# Sensor.net
KiCad netlist of a schematic drawn in Altium Designer
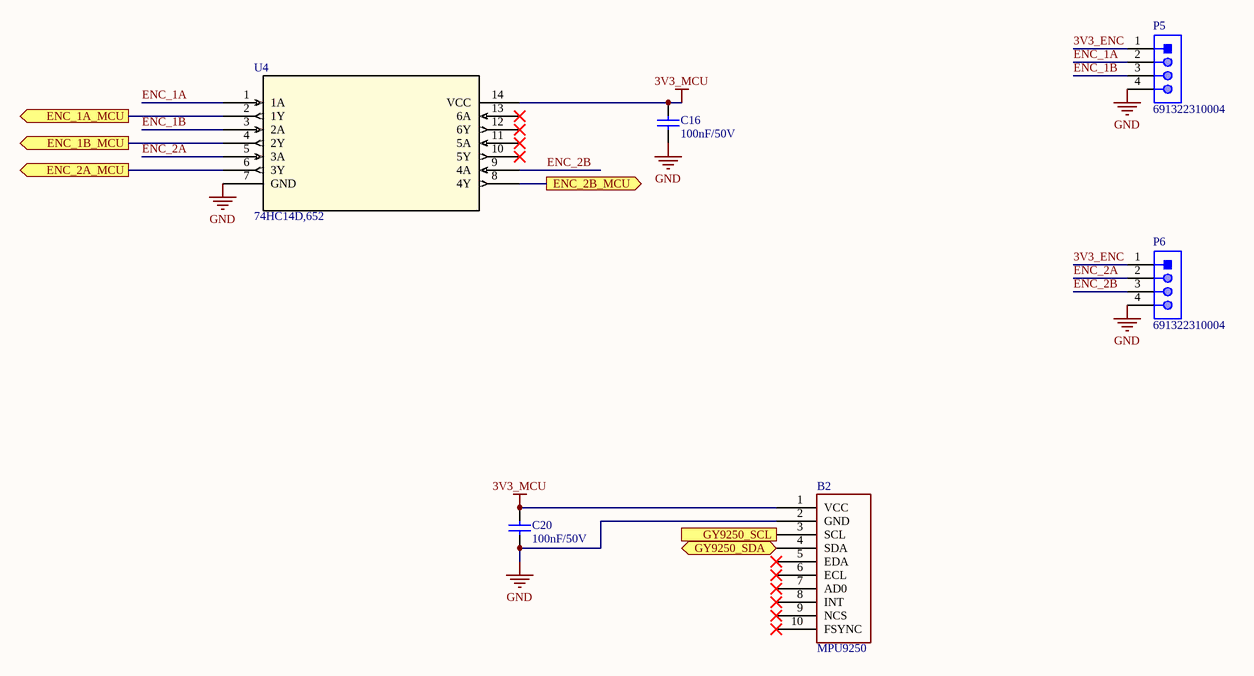
[diagram p0: Sensor.SchDoc]

(export (version "E")
  (design (tool "Eeschema 10.0.6"))
  (components
    (comp (ref "B2") (value "MPU9250") (footprint "MPU9250") (libsource (lib "Board") (part "MPU9250")))
    (comp (ref "C16")
      (value "100nF/50V")
      (footprint "CAP-SM-0805")
      (description "CAP CER 0.1UF 50V Y5V 0805")
      (fields
        (field (name "MANUFACTURER") "Samsung Electro-Mechanics")
        (field (name "MANUFACTURER PART NUMBER") "CL21F104ZBCNNNC")
      )
      (libsource (lib "Capacitor") (part "Cap-100nF-50V-0805"))
    )
    (comp (ref "C20")
      (value "100nF/50V")
      (footprint "CAP-SM-0805")
      (description "CAP CER 0.1UF 50V Y5V 0805")
      (fields
        (field (name "MANUFACTURER") "Samsung Electro-Mechanics")
        (field (name "MANUFACTURER PART NUMBER") "CL21F104ZBCNNNC")
      )
      (libsource (lib "Capacitor") (part "Cap-100nF-50V-0805"))
    )
    (comp (ref "P5")
      (value "691322310004")
      (footprint "691322310004")
      (description "WR-TBL Serie 322 Horizontal PCB Header, Pluggable, pitch 3.81mm, 4p")
      (fields (field (name "PUBLISHER") "Wurth Elektronik"))
      (libsource (lib "Domino_5mm_691101710002_Altium_WR-TBL_rev19a") (part "691322310004"))
    )
    (comp (ref "P6")
      (value "691322310004")
      (footprint "691322310004")
      (description "WR-TBL Serie 322 Horizontal PCB Header, Pluggable, pitch 3.81mm, 4p")
      (fields (field (name "PUBLISHER") "Wurth Elektronik"))
      (libsource (lib "Domino_5mm_691101710002_Altium_WR-TBL_rev19a") (part "691322310004"))
    )
    (comp (ref "U4")
      (value "74HC14D,652")
      (footprint "SOT108-1_NEX")
      (description "No Description Available")
      (fields (field (name "COPYRIGHT") "Copyright (C) 2016 Accelerated Designs. All rights reserved"))
      (libsource (lib "74HC14D_625_2020-06-19_15-46-23") (part "74HC14D,652"))
    )
  )
  (nets
    (net (code "1") (name "/3V3_ENC") (class "Default")
      (node (ref "P5") (pin "1") (pinfunction "1_1") (pintype "passive"))
      (node (ref "P6") (pin "1") (pinfunction "1_1") (pintype "passive"))
    )
    (net (code "2") (name "/ENC_1A") (class "Default")
      (node (ref "P5") (pin "2") (pinfunction "2_2") (pintype "passive"))
      (node (ref "U4") (pin "1") (pinfunction "1A_1") (pintype "input"))
    )
    (net (code "3") (name "/ENC_1A_MCU") (class "Default")
      (node (ref "U4") (pin "2") (pinfunction "1Y_2") (pintype "output"))
    )
    (net (code "4") (name "/ENC_1B") (class "Default")
      (node (ref "P5") (pin "3") (pinfunction "3_3") (pintype "passive"))
      (node (ref "U4") (pin "3") (pinfunction "2A_3") (pintype "input"))
    )
    (net (code "5") (name "/ENC_1B_MCU") (class "Default")
      (node (ref "U4") (pin "4") (pinfunction "2Y_4") (pintype "output"))
    )
    (net (code "6") (name "/ENC_2A") (class "Default")
      (node (ref "P6") (pin "2") (pinfunction "2_2") (pintype "passive"))
      (node (ref "U4") (pin "5") (pinfunction "3A_5") (pintype "input"))
    )
    (net (code "7") (name "/ENC_2A_MCU") (class "Default")
      (node (ref "U4") (pin "6") (pinfunction "3Y_6") (pintype "output"))
    )
    (net (code "8") (name "/ENC_2B") (class "Default")
      (node (ref "P6") (pin "3") (pinfunction "3_3") (pintype "passive"))
      (node (ref "U4") (pin "9") (pinfunction "4A_9") (pintype "input"))
    )
    (net (code "9") (name "/ENC_2B_MCU") (class "Default")
      (node (ref "U4") (pin "8") (pinfunction "4Y_8") (pintype "output"))
    )
    (net (code "10") (name "/GY9250_SCL") (class "Default")
      (node (ref "B2") (pin "3") (pinfunction "SCL_3") (pintype "passive"))
    )
    (net (code "11") (name "/GY9250_SDA") (class "Default")
      (node (ref "B2") (pin "4") (pinfunction "SDA_4") (pintype "passive"))
    )
    (net (code "12") (name "3V3_MCU") (class "Default")
      (node (ref "B2") (pin "1") (pinfunction "VCC_1") (pintype "passive"))
      (node (ref "C16") (pin "2") (pinfunction "2_2") (pintype "passive"))
      (node (ref "C20") (pin "2") (pinfunction "2_2") (pintype "passive"))
      (node (ref "U4") (pin "14") (pinfunction "VCC_14") (pintype "power_in"))
    )
    (net (code "13") (name "GND") (class "Default")
      (node (ref "B2") (pin "2") (pinfunction "GND_2") (pintype "passive"))
      (node (ref "C16") (pin "1") (pinfunction "1_1") (pintype "passive"))
      (node (ref "C20") (pin "1") (pinfunction "1_1") (pintype "passive"))
      (node (ref "P5") (pin "4") (pinfunction "4_4") (pintype "passive"))
      (node (ref "P6") (pin "4") (pinfunction "4_4") (pintype "passive"))
      (node (ref "U4") (pin "7") (pinfunction "GND_7") (pintype "power_in"))
    )
    (net (code "14") (name "unconnected-(B2-AD0-Pad7)") (class "Default")
      (node (ref "B2") (pin "7") (pinfunction "AD0_7") (pintype "passive+no_connect"))
    )
    (net (code "15") (name "unconnected-(B2-ECL-Pad6)") (class "Default")
      (node (ref "B2") (pin "6") (pinfunction "ECL_6") (pintype "passive+no_connect"))
    )
    (net (code "16") (name "unconnected-(B2-EDA-Pad5)") (class "Default")
      (node (ref "B2") (pin "5") (pinfunction "EDA_5") (pintype "passive+no_connect"))
    )
    (net (code "17") (name "unconnected-(B2-FSYNC-Pad10)") (class "Default")
      (node (ref "B2") (pin "10") (pinfunction "FSYNC_10") (pintype "passive+no_connect"))
    )
    (net (code "18") (name "unconnected-(B2-INT-Pad8)") (class "Default")
      (node (ref "B2") (pin "8") (pinfunction "INT_8") (pintype "passive+no_connect"))
    )
    (net (code "19") (name "unconnected-(B2-NCS-Pad9)") (class "Default")
      (node (ref "B2") (pin "9") (pinfunction "NCS_9") (pintype "passive+no_connect"))
    )
    (net (code "20") (name "unconnected-(U4-5A-Pad11)") (class "Default")
      (node (ref "U4") (pin "11") (pinfunction "5A_11") (pintype "input+no_connect"))
    )
    (net (code "21") (name "unconnected-(U4-5Y-Pad10)") (class "Default")
      (node (ref "U4") (pin "10") (pinfunction "5Y_10") (pintype "output+no_connect"))
    )
    (net (code "22") (name "unconnected-(U4-6A-Pad13)") (class "Default")
      (node (ref "U4") (pin "13") (pinfunction "6A_13") (pintype "input+no_connect"))
    )
    (net (code "23") (name "unconnected-(U4-6Y-Pad12)") (class "Default")
      (node (ref "U4") (pin "12") (pinfunction "6Y_12") (pintype "output+no_connect"))
    )
  )
)
